# SCH_GAS_DETECTION_USING_8051_2022-04-11.net
KiCad netlist of a schematic drawn in EasyEDA
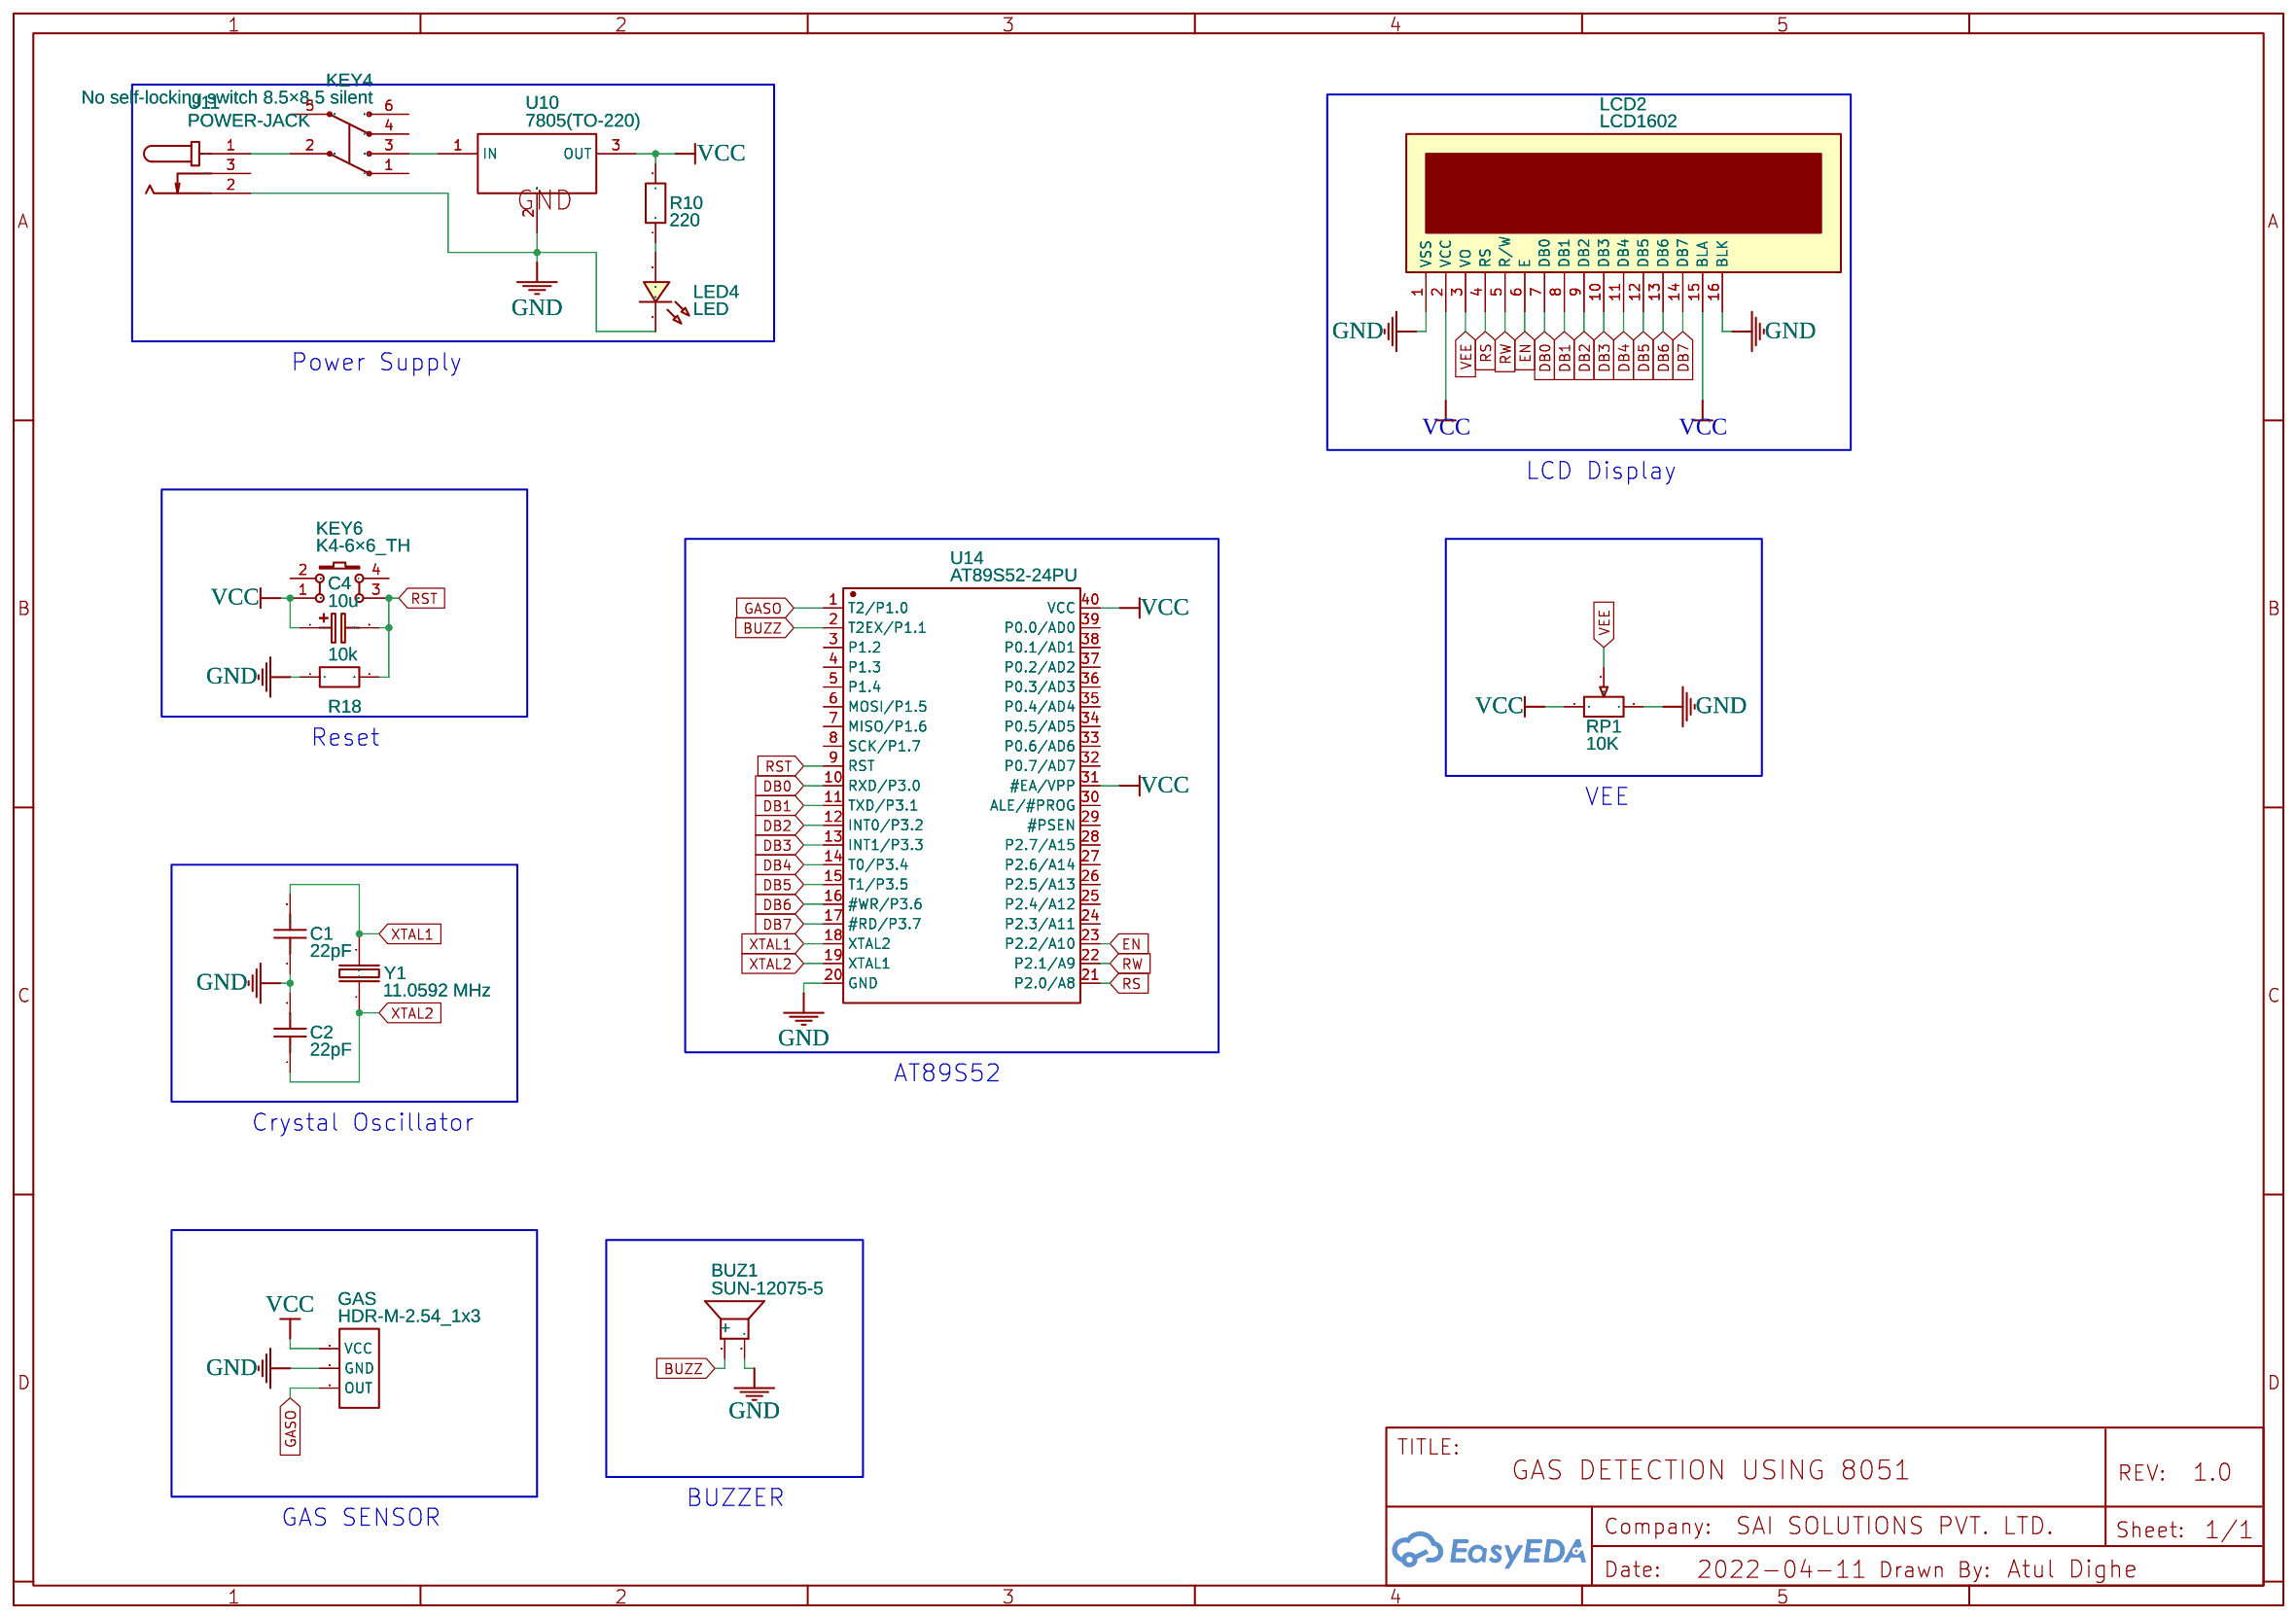
[diagram p0: schematic sheet]

(export (version "E")
  (design (tool "Eeschema 10.0.6"))
  (components
    (comp (ref "BUZ1")
      (value "SUN-12075-5")
      (fields (field (name "BOM_Supplier Part") "C2864"))
      (libsource (lib "") (part "SUN-12075-5"))
    )
    (comp (ref "C1") (value "22pF") (libsource (lib "") (part "C_RAD-0.1_US")))
    (comp (ref "C2") (value "22pF") (libsource (lib "") (part "C_RAD-0.1_US")))
    (comp (ref "C4") (value "10u") (libsource (lib "") (part "CE_TH_D8.0×F3.5_EU")))
    (comp (ref "GAS")
      (value "HDR-M-2.54_1x3")
      (fields (field (name "BOM_Supplier Part") "C180248"))
      (libsource (lib "") (part "HDR-M-2.54_1x3"))
    )
    (comp (ref "KEY4")
      (value "No self-locking switch 8.5×8.5 silent")
      (fields (field (name "BOM_Supplier Part") "C26228"))
      (libsource (lib "") (part "No self-locking switch 8.5×8.5 silent"))
    )
    (comp (ref "KEY6")
      (value "K4-6×6_TH")
      (fields
        (field (name "BOM_Manufacturer Part") "K2-1102DP-E4SW-04")
        (field (name "BOM_Supplier Part") "C136684")
      )
      (libsource (lib "") (part "K4-6×6_TH"))
    )
    (comp (ref "LCD2")
      (value "LCD1602")
      (fields
        (field (name "BOM_Manufacturer Part") "LCM1602K-NSW-BBW")
        (field (name "BOM_Supplier Part") "C83275")
      )
      (libsource (lib "") (part "LCD1602"))
    )
    (comp (ref "LED4")
      (value "LED")
      (fields
        (field (name "BOM_Manufacturer Part") "204-10SDRD/S530-A3-L")
        (field (name "BOM_Supplier Part") "C84774")
      )
      (libsource (lib "") (part "LED-TH-3mm_R"))
    )
    (comp (ref "R10") (value "220") (libsource (lib "") (part "R_AXIAL-0.3_EU")))
    (comp (ref "R18") (value "10k") (libsource (lib "") (part "R_AXIAL-0.3_EU_1")))
    (comp (ref "RP1") (value "10K") (libsource (lib "") (part "R_3386P_EU")))
    (comp (ref "U10")
      (value "7805(TO-220)")
      (fields (field (name "BOM_Manufacturer Part") "L7805CV-DG") (field (name "BOM_Supplier Part") "C3795"))
      (libsource (lib "") (part "7805(TO-220)"))
    )
    (comp (ref "U11")
      (value "POWER-JACK")
      (fields (field (name "BOM_Supplier Part") "C9900001795"))
      (libsource (lib "") (part "POWER-JACK"))
    )
    (comp (ref "U14")
      (value "AT89S52-24PU")
      (fields (field (name "BOM_Supplier Part") "C9441"))
      (libsource (lib "") (part "AT89S52-24PU"))
    )
    (comp (ref "Y1") (value "11.0592 MHz") (libsource (lib "") (part "?MHz")))
  )
  (nets
    (net (code "1") (name "BUZZ") (class "Default")
      (node (ref "BUZ1") (pin "1") (pinfunction "+_1") (pintype "unspecified"))
      (node (ref "U14") (pin "2") (pinfunction "T2EX/P1.1_2") (pintype "unspecified"))
    )
    (net (code "2") (name "DB0") (class "Default")
      (node (ref "LCD2") (pin "7") (pinfunction "DB0_7") (pintype "unspecified"))
      (node (ref "U14") (pin "10") (pinfunction "RXD/P3.0_10") (pintype "unspecified"))
    )
    (net (code "3") (name "DB1") (class "Default")
      (node (ref "LCD2") (pin "8") (pinfunction "DB1_8") (pintype "unspecified"))
      (node (ref "U14") (pin "11") (pinfunction "TXD/P3.1_11") (pintype "unspecified"))
    )
    (net (code "4") (name "DB2") (class "Default")
      (node (ref "LCD2") (pin "9") (pinfunction "DB2_9") (pintype "unspecified"))
      (node (ref "U14") (pin "12") (pinfunction "INT0/P3.2_12") (pintype "unspecified"))
    )
    (net (code "5") (name "DB3") (class "Default")
      (node (ref "LCD2") (pin "10") (pinfunction "DB3_10") (pintype "unspecified"))
      (node (ref "U14") (pin "13") (pinfunction "INT1/P3.3_13") (pintype "unspecified"))
    )
    (net (code "6") (name "DB4") (class "Default")
      (node (ref "LCD2") (pin "11") (pinfunction "DB4_11") (pintype "unspecified"))
      (node (ref "U14") (pin "14") (pinfunction "T0/P3.4_14") (pintype "unspecified"))
    )
    (net (code "7") (name "DB5") (class "Default")
      (node (ref "LCD2") (pin "12") (pinfunction "DB5_12") (pintype "unspecified"))
      (node (ref "U14") (pin "15") (pinfunction "T1/P3.5_15") (pintype "unspecified"))
    )
    (net (code "8") (name "DB6") (class "Default")
      (node (ref "LCD2") (pin "13") (pinfunction "DB6_13") (pintype "unspecified"))
      (node (ref "U14") (pin "16") (pinfunction "#WR/P3.6_16") (pintype "unspecified"))
    )
    (net (code "9") (name "DB7") (class "Default")
      (node (ref "LCD2") (pin "14") (pinfunction "DB7_14") (pintype "unspecified"))
      (node (ref "U14") (pin "17") (pinfunction "#RD/P3.7_17") (pintype "unspecified"))
    )
    (net (code "10") (name "EN") (class "Default")
      (node (ref "LCD2") (pin "6") (pinfunction "E_6") (pintype "unspecified"))
      (node (ref "U14") (pin "23") (pinfunction "P2.2/A10_23") (pintype "unspecified"))
    )
    (net (code "11") (name "GASO") (class "Default")
      (node (ref "GAS") (pin "3") (pinfunction "OUT_3") (pintype "input"))
      (node (ref "U14") (pin "1") (pinfunction "T2/P1.0_1") (pintype "unspecified"))
    )
    (net (code "12") (name "GND") (class "Default")
      (node (ref "BUZ1") (pin "2") (pinfunction "2_2") (pintype "unspecified"))
      (node (ref "C1") (pin "1") (pinfunction "1_1") (pintype "unspecified"))
      (node (ref "C2") (pin "2") (pinfunction "2_2") (pintype "unspecified"))
      (node (ref "GAS") (pin "2") (pinfunction "GND_2") (pintype "input"))
      (node (ref "LCD2") (pin "1") (pinfunction "VSS_1") (pintype "unspecified"))
      (node (ref "LCD2") (pin "16") (pinfunction "BLK_16") (pintype "unspecified"))
      (node (ref "LED4") (pin "2") (pinfunction "2_2") (pintype "unspecified"))
      (node (ref "R18") (pin "1") (pinfunction "1_1") (pintype "unspecified"))
      (node (ref "RP1") (pin "3") (pinfunction "3_3") (pintype "input"))
      (node (ref "U10") (pin "2") (pinfunction "GND_2") (pintype "passive"))
      (node (ref "U11") (pin "2") (pinfunction "2_2") (pintype "unspecified"))
      (node (ref "U14") (pin "20") (pinfunction "GND_20") (pintype "unspecified"))
    )
    (net (code "13") (name "Net-(KEY4-Pad2)") (class "Default")
      (node (ref "KEY4") (pin "2") (pinfunction "2_2") (pintype "unspecified"))
      (node (ref "U11") (pin "1") (pinfunction "1_1") (pintype "unspecified"))
    )
    (net (code "14") (name "Net-(LED4-Pad1)") (class "Default")
      (node (ref "LED4") (pin "1") (pinfunction "1_1") (pintype "unspecified"))
      (node (ref "R10") (pin "1") (pinfunction "1_1") (pintype "unspecified"))
    )
    (net (code "15") (name "Net-(U10-IN)") (class "Default")
      (node (ref "KEY4") (pin "3") (pinfunction "3_3") (pintype "unspecified"))
      (node (ref "U10") (pin "1") (pinfunction "IN_1") (pintype "passive"))
    )
    (net (code "16") (name "RS") (class "Default")
      (node (ref "LCD2") (pin "4") (pinfunction "RS_4") (pintype "unspecified"))
      (node (ref "U14") (pin "21") (pinfunction "P2.0/A8_21") (pintype "unspecified"))
    )
    (net (code "17") (name "RST") (class "Default")
      (node (ref "C4") (pin "2") (pinfunction "2_2") (pintype "unspecified"))
      (node (ref "KEY6") (pin "3") (pinfunction "3_3") (pintype "unspecified"))
      (node (ref "R18") (pin "2") (pinfunction "2_2") (pintype "unspecified"))
      (node (ref "U14") (pin "9") (pinfunction "RST_9") (pintype "unspecified"))
    )
    (net (code "18") (name "RW") (class "Default")
      (node (ref "LCD2") (pin "5") (pinfunction "R/W_5") (pintype "unspecified"))
      (node (ref "U14") (pin "22") (pinfunction "P2.1/A9_22") (pintype "unspecified"))
    )
    (net (code "19") (name "VCC") (class "Default")
      (node (ref "C4") (pin "1") (pinfunction "1_1") (pintype "unspecified"))
      (node (ref "GAS") (pin "1") (pinfunction "VCC_1") (pintype "input"))
      (node (ref "KEY6") (pin "1") (pinfunction "1_1") (pintype "unspecified"))
      (node (ref "LCD2") (pin "15") (pinfunction "BLA_15") (pintype "unspecified"))
      (node (ref "LCD2") (pin "2") (pinfunction "VCC_2") (pintype "unspecified"))
      (node (ref "R10") (pin "2") (pinfunction "2_2") (pintype "unspecified"))
      (node (ref "RP1") (pin "1") (pinfunction "1_1") (pintype "input"))
      (node (ref "U10") (pin "3") (pinfunction "OUT_3") (pintype "passive"))
      (node (ref "U14") (pin "31") (pinfunction "#EA/VPP_31") (pintype "unspecified"))
      (node (ref "U14") (pin "40") (pinfunction "VCC_40") (pintype "unspecified"))
    )
    (net (code "20") (name "VEE") (class "Default")
      (node (ref "LCD2") (pin "3") (pinfunction "VO_3") (pintype "unspecified"))
      (node (ref "RP1") (pin "2") (pinfunction "2_2") (pintype "input"))
    )
    (net (code "21") (name "XTAL1") (class "Default")
      (node (ref "C1") (pin "2") (pinfunction "2_2") (pintype "unspecified"))
      (node (ref "U14") (pin "18") (pinfunction "XTAL2_18") (pintype "unspecified"))
      (node (ref "Y1") (pin "2") (pinfunction "2_2") (pintype "unspecified"))
    )
    (net (code "22") (name "XTAL2") (class "Default")
      (node (ref "C2") (pin "1") (pinfunction "1_1") (pintype "unspecified"))
      (node (ref "U14") (pin "19") (pinfunction "XTAL1_19") (pintype "unspecified"))
      (node (ref "Y1") (pin "1") (pinfunction "1_1") (pintype "unspecified"))
    )
    (net (code "23") (name "unconnected-(KEY4-Pad1)") (class "Default")
      (node (ref "KEY4") (pin "1") (pinfunction "1_1") (pintype "unspecified"))
    )
    (net (code "24") (name "unconnected-(KEY4-Pad4)") (class "Default")
      (node (ref "KEY4") (pin "4") (pinfunction "4_4") (pintype "unspecified"))
    )
    (net (code "25") (name "unconnected-(KEY4-Pad5)") (class "Default")
      (node (ref "KEY4") (pin "5") (pinfunction "5_5") (pintype "unspecified"))
    )
    (net (code "26") (name "unconnected-(KEY4-Pad6)") (class "Default")
      (node (ref "KEY4") (pin "6") (pinfunction "6_6") (pintype "unspecified"))
    )
    (net (code "27") (name "unconnected-(KEY6-Pad2)") (class "Default")
      (node (ref "KEY6") (pin "2") (pinfunction "2_2") (pintype "unspecified"))
    )
    (net (code "28") (name "unconnected-(KEY6-Pad4)") (class "Default")
      (node (ref "KEY6") (pin "4") (pinfunction "4_4") (pintype "unspecified"))
    )
    (net (code "29") (name "unconnected-(U11-Pad3)") (class "Default")
      (node (ref "U11") (pin "3") (pinfunction "3_3") (pintype "unspecified"))
    )
    (net (code "30") (name "unconnected-(U14-#PSEN-Pad29)") (class "Default")
      (node (ref "U14") (pin "29") (pinfunction "#PSEN_29") (pintype "unspecified"))
    )
    (net (code "31") (name "unconnected-(U14-ALE{slash}#PROG-Pad30)") (class "Default")
      (node (ref "U14") (pin "30") (pinfunction "ALE/#PROG_30") (pintype "unspecified"))
    )
    (net (code "32") (name "unconnected-(U14-MISO{slash}P1.6-Pad7)") (class "Default")
      (node (ref "U14") (pin "7") (pinfunction "MISO/P1.6_7") (pintype "unspecified"))
    )
    (net (code "33") (name "unconnected-(U14-MOSI{slash}P1.5-Pad6)") (class "Default")
      (node (ref "U14") (pin "6") (pinfunction "MOSI/P1.5_6") (pintype "unspecified"))
    )
    (net (code "34") (name "unconnected-(U14-P0.0{slash}AD0-Pad39)") (class "Default")
      (node (ref "U14") (pin "39") (pinfunction "P0.0/AD0_39") (pintype "unspecified"))
    )
    (net (code "35") (name "unconnected-(U14-P0.1{slash}AD1-Pad38)") (class "Default")
      (node (ref "U14") (pin "38") (pinfunction "P0.1/AD1_38") (pintype "unspecified"))
    )
    (net (code "36") (name "unconnected-(U14-P0.2{slash}AD2-Pad37)") (class "Default")
      (node (ref "U14") (pin "37") (pinfunction "P0.2/AD2_37") (pintype "unspecified"))
    )
    (net (code "37") (name "unconnected-(U14-P0.3{slash}AD3-Pad36)") (class "Default")
      (node (ref "U14") (pin "36") (pinfunction "P0.3/AD3_36") (pintype "unspecified"))
    )
    (net (code "38") (name "unconnected-(U14-P0.4{slash}AD4-Pad35)") (class "Default")
      (node (ref "U14") (pin "35") (pinfunction "P0.4/AD4_35") (pintype "unspecified"))
    )
    (net (code "39") (name "unconnected-(U14-P0.5{slash}AD5-Pad34)") (class "Default")
      (node (ref "U14") (pin "34") (pinfunction "P0.5/AD5_34") (pintype "unspecified"))
    )
    (net (code "40") (name "unconnected-(U14-P0.6{slash}AD6-Pad33)") (class "Default")
      (node (ref "U14") (pin "33") (pinfunction "P0.6/AD6_33") (pintype "unspecified"))
    )
    (net (code "41") (name "unconnected-(U14-P0.7{slash}AD7-Pad32)") (class "Default")
      (node (ref "U14") (pin "32") (pinfunction "P0.7/AD7_32") (pintype "unspecified"))
    )
    (net (code "42") (name "unconnected-(U14-P1.2-Pad3)") (class "Default")
      (node (ref "U14") (pin "3") (pinfunction "P1.2_3") (pintype "unspecified"))
    )
    (net (code "43") (name "unconnected-(U14-P1.3-Pad4)") (class "Default")
      (node (ref "U14") (pin "4") (pinfunction "P1.3_4") (pintype "unspecified"))
    )
    (net (code "44") (name "unconnected-(U14-P1.4-Pad5)") (class "Default")
      (node (ref "U14") (pin "5") (pinfunction "P1.4_5") (pintype "unspecified"))
    )
    (net (code "45") (name "unconnected-(U14-P2.3{slash}A11-Pad24)") (class "Default")
      (node (ref "U14") (pin "24") (pinfunction "P2.3/A11_24") (pintype "unspecified"))
    )
    (net (code "46") (name "unconnected-(U14-P2.4{slash}A12-Pad25)") (class "Default")
      (node (ref "U14") (pin "25") (pinfunction "P2.4/A12_25") (pintype "unspecified"))
    )
    (net (code "47") (name "unconnected-(U14-P2.5{slash}A13-Pad26)") (class "Default")
      (node (ref "U14") (pin "26") (pinfunction "P2.5/A13_26") (pintype "unspecified"))
    )
    (net (code "48") (name "unconnected-(U14-P2.6{slash}A14-Pad27)") (class "Default")
      (node (ref "U14") (pin "27") (pinfunction "P2.6/A14_27") (pintype "unspecified"))
    )
    (net (code "49") (name "unconnected-(U14-P2.7{slash}A15-Pad28)") (class "Default")
      (node (ref "U14") (pin "28") (pinfunction "P2.7/A15_28") (pintype "unspecified"))
    )
    (net (code "50") (name "unconnected-(U14-SCK{slash}P1.7-Pad8)") (class "Default")
      (node (ref "U14") (pin "8") (pinfunction "SCK/P1.7_8") (pintype "unspecified"))
    )
  )
)
